# AS5147.net
KiCad netlist of a schematic drawn in Altium Designer
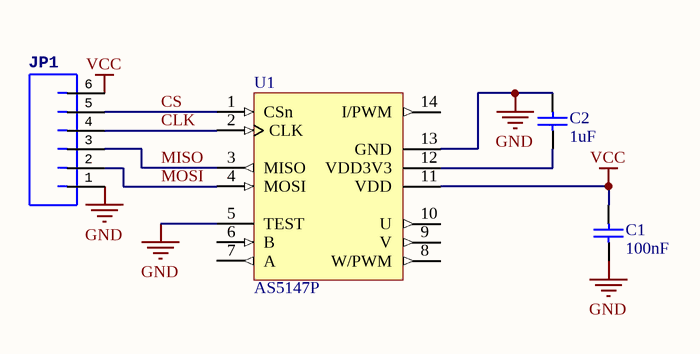
[diagram p0: AS5147.SchDoc]

(export (version "E")
  (design (tool "Eeschema 10.0.6"))
  (components
    (comp (ref "C1")
      (value "100nF")
      (footprint "CAPC0402(1005)60_L")
      (description "CAP 100nF 6.3V ±5% 0402 (1005 Metric) Thickness 0.6mm SMD")
      (fields (field (name "TOLERANCE") "Â±5%"))
      (libsource (lib "Altium Content Vault") (part "CMP-1034-02060-1"))
    )
    (comp (ref "C2")
      (value "1uF")
      (footprint "CAPC0402(1005)60_L")
      (description "CAP 1uF 6.3V ±10% 0402 (1005 Metric) Thickness 0.6mm SMD")
      (fields (field (name "TOLERANCE") "Â±10%"))
      (libsource (lib "Altium Content Vault") (part "CMP-1034-02113-1"))
    )
    (comp (ref "JP1") (value "~") (footprint "JST-6-SMD") (libsource (lib "Components") (part "JST_6")))
    (comp (ref "U1")
      (value "AS5147P")
      (footprint "AMS-TSSOP-14-5000X4400DE_N")
      (libsource (lib "Components") (part "AMS-AS5147P"))
    )
  )
  (nets
    (net (code "1") (name "/CLK") (class "Default")
      (node (ref "JP1") (pin "4") (pinfunction "4_4") (pintype "passive"))
      (node (ref "U1") (pin "2") (pinfunction "CLK_2") (pintype "input"))
    )
    (net (code "2") (name "/CS") (class "Default")
      (node (ref "JP1") (pin "5") (pinfunction "5_5") (pintype "passive"))
      (node (ref "U1") (pin "1") (pinfunction "CSn_1") (pintype "input"))
    )
    (net (code "3") (name "/MISO") (class "Default")
      (node (ref "JP1") (pin "3") (pinfunction "3_3") (pintype "passive"))
      (node (ref "U1") (pin "3") (pinfunction "MISO_3") (pintype "output"))
    )
    (net (code "4") (name "/MOSI") (class "Default")
      (node (ref "JP1") (pin "2") (pinfunction "2_2") (pintype "passive"))
      (node (ref "U1") (pin "4") (pinfunction "MOSI_4") (pintype "input"))
    )
    (net (code "5") (name "GND") (class "Default")
      (node (ref "C1") (pin "1") (pinfunction "1_1") (pintype "passive"))
      (node (ref "C2") (pin "1") (pinfunction "1_1") (pintype "passive"))
      (node (ref "JP1") (pin "1") (pinfunction "1_1") (pintype "passive"))
      (node (ref "U1") (pin "13") (pinfunction "GND_13") (pintype "power_in"))
      (node (ref "U1") (pin "5") (pinfunction "TEST_5") (pintype "passive"))
    )
    (net (code "6") (name "Net-(U1-VDD3V3)") (class "Default")
      (node (ref "C2") (pin "2") (pinfunction "2_2") (pintype "passive"))
      (node (ref "U1") (pin "12") (pinfunction "VDD3V3_12") (pintype "power_in"))
    )
    (net (code "7") (name "VCC") (class "Default")
      (node (ref "C1") (pin "2") (pinfunction "2_2") (pintype "passive"))
      (node (ref "JP1") (pin "6") (pinfunction "6_6") (pintype "passive"))
      (node (ref "U1") (pin "11") (pinfunction "VDD_11") (pintype "power_in"))
    )
    (net (code "8") (name "unconnected-(U1-A-Pad7)") (class "Default")
      (node (ref "U1") (pin "7") (pinfunction "A_7") (pintype "output"))
    )
    (net (code "9") (name "unconnected-(U1-B-Pad6)") (class "Default")
      (node (ref "U1") (pin "6") (pinfunction "B_6") (pintype "input"))
    )
    (net (code "10") (name "unconnected-(U1-I{slash}PWM-Pad14)") (class "Default")
      (node (ref "U1") (pin "14") (pinfunction "I/PWM_14") (pintype "output"))
    )
    (net (code "11") (name "unconnected-(U1-U-Pad10)") (class "Default")
      (node (ref "U1") (pin "10") (pinfunction "U_10") (pintype "output"))
    )
    (net (code "12") (name "unconnected-(U1-V-Pad9)") (class "Default")
      (node (ref "U1") (pin "9") (pinfunction "V_9") (pintype "output"))
    )
    (net (code "13") (name "unconnected-(U1-W{slash}PWM-Pad8)") (class "Default")
      (node (ref "U1") (pin "8") (pinfunction "W/PWM_8") (pintype "output"))
    )
  )
)
